# Battery_Charger.net
KiCad netlist of a schematic drawn in Altium Designer
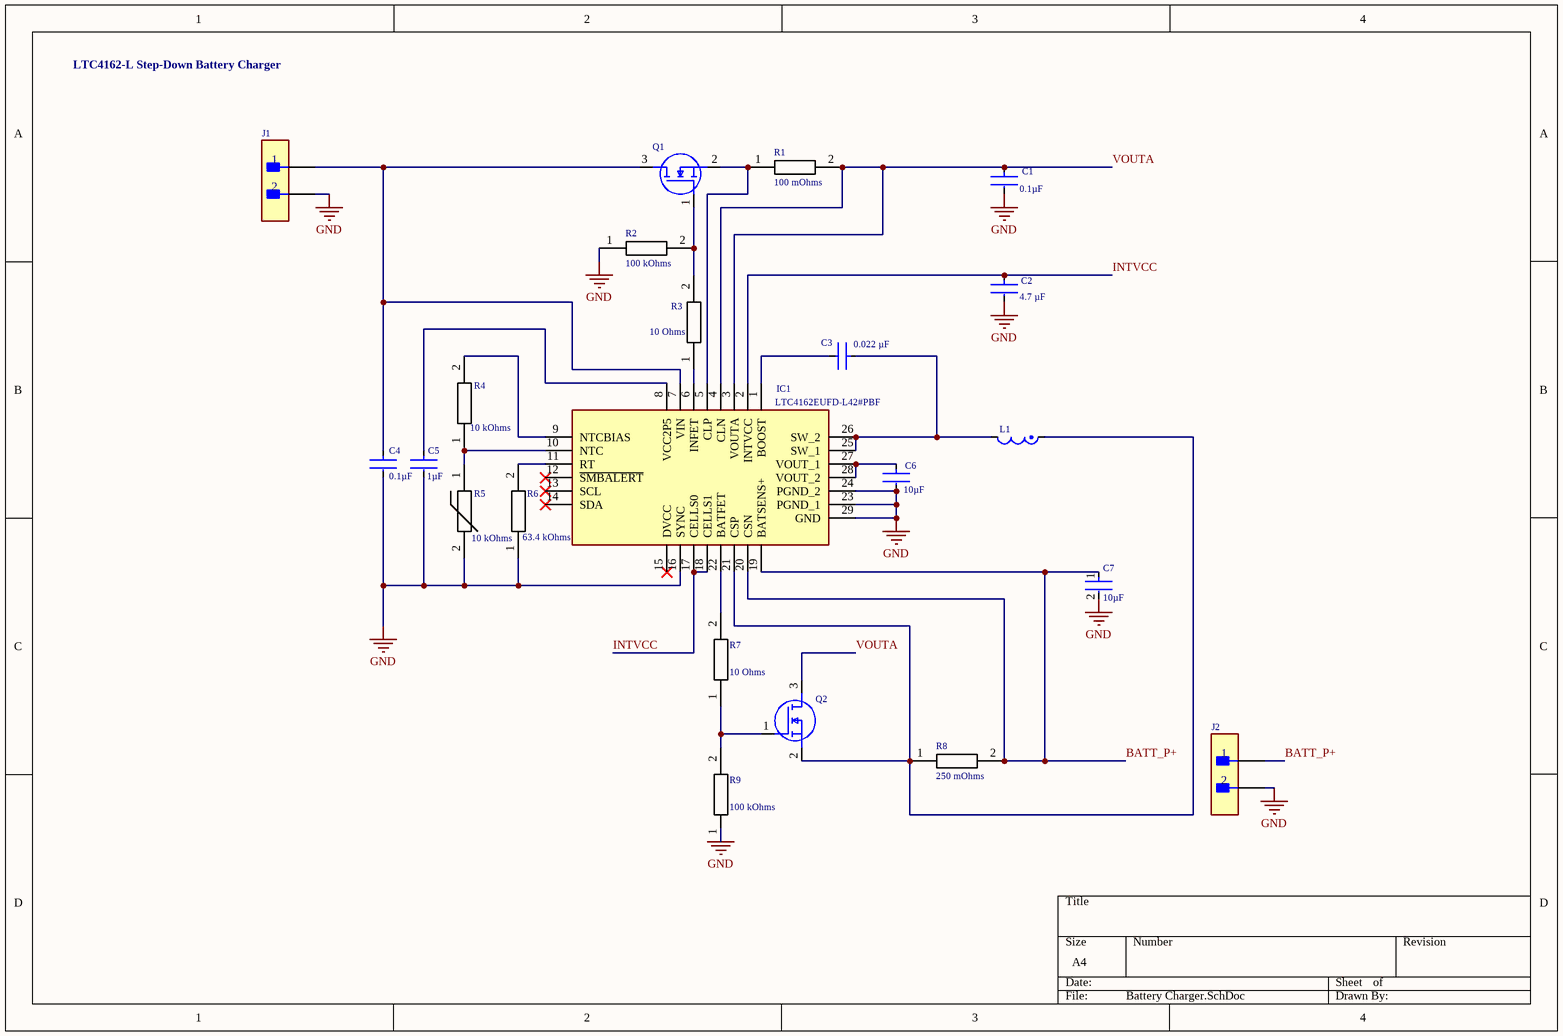
[diagram p0: Battery Charger.SchDoc]

(export (version "E")
  (design (tool "Eeschema 10.0.6"))
  (components
    (comp (ref "C1")
      (value "0.1µF")
      (footprint "FP-CC0603-DA-MFG")
      (description "CAP CER 0.1UF 16V X7R 0603 CC0603KRX7R7BB104")
      (fields
        (field (name "OCTOPART") "https://octopart.com/cc0603krx7r7bb104-yageo-192941")
        (field (name "TOLERANCE") "0.1")
      )
      (libsource (lib "Altium Content Vault") (part "11868f565c42a9108669ba33697ecf6"))
    )
    (comp (ref "C2")
      (value "4.7 µF")
      (footprint "FP-CC0603-DA-MFG")
      (description "CAP CER 4.7UF 10V X5R 0603 CC0603KRX5R6BB475")
      (fields (field (name "MANUFACTURER PART NUMBER") "CC0603KRX5R6BB475") (field (name "VOLTAGE") "10 V"))
      (libsource (lib "Altium Content Vault") (part "11868f565c42a9108669ba33697ecf6"))
    )
    (comp (ref "C3")
      (value "0.022 µF")
      (footprint "FP-C0603C-CF-MFG")
      (description "Ceramic Capacitor 0.022Uf 16V, X7R, 10%, 0603, Full Reel C0603C223K4RACTU")
      (fields
        (field (name "OCTOPART") "https://octopart.com/c0603c223k4ractu-kemet-123286")
        (field (name "MANUFACTURER PART NUMBER") "C0603C223K4RACTU")
      )
      (libsource (lib "Altium Content Vault") (part "b4654b650e69147ec39a6b967a45e02"))
    )
    (comp (ref "C4")
      (value "0.1µF")
      (footprint "FP-CC0603-DA-MFG")
      (description "CAP CER 0.1UF 16V X7R 0603 CC0603KRX7R7BB104")
      (fields
        (field (name "OCTOPART") "https://octopart.com/cc0603krx7r7bb104-yageo-192941")
        (field (name "TOLERANCE") "0.1")
      )
      (libsource (lib "Altium Content Vault") (part "11868f565c42a9108669ba33697ecf6"))
    )
    (comp (ref "C5")
      (value "1µF")
      (footprint "FP-CC0603-DA-MFG")
      (description "CAP CER 1UF 25V X5R 0603 CC0603KRX5R8BB105")
      (fields
        (field (name "OCTOPART") "https://octopart.com/cc0603krx5r8bb105-yageo-9292811")
        (field (name "MANUFACTURER") "YAGEO")
      )
      (libsource (lib "Altium Content Vault") (part "11868f565c42a9108669ba33697ecf6"))
    )
    (comp (ref "C6")
      (value "10µF")
      (footprint "FP-GRM21B-0_1-MFG")
      (fields (field (name "TOLERANCE") "10%") (field (name "VOLTAGE") "16V"))
      (libsource (lib "Altium Content Vault") (part "b4654b650e69147ec39a6b967a45e02"))
    )
    (comp (ref "C7")
      (value "10µF")
      (footprint "FP-GRM21B-0_1-MFG")
      (fields (field (name "TOLERANCE") "10%") (field (name "VOLTAGE") "16V"))
      (libsource (lib "") (part "b4654b650e69147ec39a6b967a45e02_1"))
    )
    (comp (ref "IC1")
      (value "LTC4162EUFD-L42#PBF")
      (footprint "SamacSys:QFN50P400X500X80-29N-D")
      (description "Integrated Circuit")
      (fields (field (name "MOUSER PART NUMBER") "584-4162EUFDL42PB"))
      (libsource (lib "SamacSys") (part "LTC4162EUFD-L42#PBF"))
    )
    (comp (ref "J1")
      (value "B2B-XH-A(LF)(SN)")
      (footprint "FP-B2B-XH-A_LF_SN-MFG")
      (description "CONN HEADER VERT 2POS 2.5MM")
      (libsource (lib "Altium Content Vault") (part "3bc925449376181038e59eaffc5286c"))
    )
    (comp (ref "J2")
      (value "B2B-XH-A(LF)(SN)")
      (footprint "FP-B2B-XH-A_LF_SN-MFG")
      (description "CONN HEADER VERT 2POS 2.5MM")
      (libsource (lib "Altium Content Vault") (part "3bc925449376181038e59eaffc5286c"))
    )
    (comp (ref "L1")
      (value "#B952AS-H-1R1N=P3")
      (footprint "FP-DS104C2-MFG")
      (description "Shielded Wirewound Inductor 1.1uH 30% 6000mA 0.011Ω SMD")
      (fields (field (name "TOLERANCE") "30%"))
      (libsource (lib "Altium Content Vault") (part "ae3b6ca10b736fc74204ce580bf9b8e"))
    )
    (comp (ref "Q1")
      (value "IRLML6344TRPBF")
      (footprint "SamacSys:SOT95P237X112-3N")
      (description "MOSFET (N-Channel)")
      (fields (field (name "MOUSER PART NUMBER") "942-IRLML6344TRPBF"))
      (libsource (lib "SamacSys") (part "IRLML6344TRPBF"))
    )
    (comp (ref "Q2")
      (value "IRLML6344TRPBF")
      (footprint "SamacSys:SOT95P237X112-3N")
      (description "MOSFET (N-Channel)")
      (fields (field (name "MOUSER PART NUMBER") "942-IRLML6344TRPBF"))
      (libsource (lib "SamacSys") (part "IRLML6344TRPBF"))
    )
    (comp (ref "R1")
      (value "100 mOhms")
      (footprint "PcbLib1:WSL2512R1000FEA Resistor")
      (libsource (lib "resistors") (part "WSL2512R1000FEA Resistor"))
    )
    (comp (ref "R2")
      (value "100 kOhms")
      (footprint "RC0603FR-07100KL Resistor")
      (description "100 kOhms ±1% 0.1W, 1/10W Chip Resistor 0603 (1608 Metric) Moisture Resistant Thick Film")
      (libsource (lib "resistors") (part "RC0603FR-07100KL Resistor"))
    )
    (comp (ref "R3")
      (value "10 Ohms")
      (footprint "RC0603FR-0710RL Resistor")
      (description "10 Ohms ±1% 0.1W, 1/10W Chip Resistor 0603 (1608 Metric) Moisture Resistant Thick Film")
      (libsource (lib "resistors") (part "RC0603FR-0710RL Resistor"))
    )
    (comp (ref "R4")
      (value "10 kOhms")
      (footprint "RC0603FR-0710KL")
      (description "10 kOhms ±1% 0.1W, 1/10W Chip Resistor 0603 (1608 Metric) Moisture Resistant Thick Film")
      (libsource (lib "resistors") (part "RC0603FR-0710KL Resistor"))
    )
    (comp (ref "R5")
      (value "10 kOhms")
      (footprint "NCP18XH103F03RB")
      (description "THERMISTOR NTC 10KOHM 3380K 0603")
      (libsource (lib "resistors") (part "NCP18XH103F03RB Resistor"))
    )
    (comp (ref "R6")
      (value "63.4 kOhms")
      (footprint "SamacSys:RESC1608X55N")
      (description "RC0603FR-0763K4L")
      (fields (field (name "MOUSER PART NUMBER") "603-RC0603FR-0763K4L"))
      (libsource (lib "*") (part "RC0603FR-0763K4L"))
    )
    (comp (ref "R7")
      (value "10 Ohms")
      (footprint "RC0603FR-0710RL Resistor")
      (description "10 Ohms ±1% 0.1W, 1/10W Chip Resistor 0603 (1608 Metric) Moisture Resistant Thick Film")
      (libsource (lib "resistors") (part "RC0603FR-0710RL Resistor"))
    )
    (comp (ref "R8")
      (value "250 mOhms")
      (footprint "SamacSys:RESC3216X89N")
      (description "WSL1206R2500FEA")
      (fields (field (name "MOUSER PART NUMBER") "71-WSL1206R2500FEA"))
      (libsource (lib "*") (part "WSL1206R2500FEA"))
    )
    (comp (ref "R9")
      (value "100 kOhms")
      (footprint "RC0603FR-07100KL Resistor")
      (description "100 kOhms ±1% 0.1W, 1/10W Chip Resistor 0603 (1608 Metric) Moisture Resistant Thick Film")
      (libsource (lib "resistors") (part "RC0603FR-07100KL Resistor"))
    )
  )
  (nets
    (net (code "1") (name "/BATT_P+") (class "Default")
      (node (ref "C7") (pin "1") (pinfunction "1_1") (pintype "passive"))
      (node (ref "IC1") (pin "19") (pinfunction "BATSENS+_19") (pintype "passive"))
      (node (ref "IC1") (pin "20") (pinfunction "CSN_20") (pintype "passive"))
      (node (ref "J2") (pin "1") (pinfunction "1_1") (pintype "passive"))
      (node (ref "R8") (pin "2") (pinfunction "2_2") (pintype "passive"))
    )
    (net (code "2") (name "/INTVCC") (class "Default")
      (node (ref "C2") (pin "1") (pinfunction "1_1") (pintype "passive"))
      (node (ref "IC1") (pin "17") (pinfunction "CELLS0_17") (pintype "passive"))
      (node (ref "IC1") (pin "18") (pinfunction "CELLS1_18") (pintype "passive"))
      (node (ref "IC1") (pin "2") (pinfunction "INTVCC_2") (pintype "passive"))
    )
    (net (code "3") (name "/VOUTA") (class "Default")
      (node (ref "C1") (pin "1") (pinfunction "1_1") (pintype "passive"))
      (node (ref "IC1") (pin "3") (pinfunction "VOUTA_3") (pintype "passive"))
      (node (ref "IC1") (pin "4") (pinfunction "CLN_4") (pintype "passive"))
      (node (ref "Q2") (pin "3") (pinfunction "D_3") (pintype "passive"))
      (node (ref "R1") (pin "2") (pinfunction "2_2") (pintype "passive"))
    )
    (net (code "4") (name "GND") (class "Default")
      (node (ref "C1") (pin "2") (pinfunction "2_2") (pintype "passive"))
      (node (ref "C2") (pin "2") (pinfunction "2_2") (pintype "passive"))
      (node (ref "C4") (pin "2") (pinfunction "2_2") (pintype "passive"))
      (node (ref "C5") (pin "2") (pinfunction "2_2") (pintype "passive"))
      (node (ref "C6") (pin "2") (pinfunction "2_2") (pintype "passive"))
      (node (ref "C7") (pin "2") (pinfunction "2_2") (pintype "passive"))
      (node (ref "IC1") (pin "16") (pinfunction "SYNC_16") (pintype "passive"))
      (node (ref "IC1") (pin "23") (pinfunction "PGND_1_23") (pintype "passive"))
      (node (ref "IC1") (pin "24") (pinfunction "PGND_2_24") (pintype "passive"))
      (node (ref "IC1") (pin "29") (pinfunction "GND_29") (pintype "passive"))
      (node (ref "J1") (pin "2") (pinfunction "2_2") (pintype "passive"))
      (node (ref "J2") (pin "2") (pinfunction "2_2") (pintype "passive"))
      (node (ref "R2") (pin "1") (pinfunction "1_1") (pintype "passive"))
      (node (ref "R5") (pin "2") (pinfunction "2_2") (pintype "passive"))
      (node (ref "R6") (pin "1") (pinfunction "1_1") (pintype "passive"))
      (node (ref "R9") (pin "1") (pinfunction "1_1") (pintype "passive"))
    )
    (net (code "5") (name "Net-(IC1-BATFET)") (class "Default")
      (node (ref "IC1") (pin "22") (pinfunction "BATFET_22") (pintype "passive"))
      (node (ref "R7") (pin "2") (pinfunction "2_2") (pintype "passive"))
    )
    (net (code "6") (name "Net-(IC1-BOOST)") (class "Default")
      (node (ref "C3") (pin "2") (pinfunction "2_2") (pintype "passive"))
      (node (ref "IC1") (pin "1") (pinfunction "BOOST_1") (pintype "passive"))
    )
    (net (code "7") (name "Net-(IC1-CLP)") (class "Default")
      (node (ref "IC1") (pin "5") (pinfunction "CLP_5") (pintype "passive"))
      (node (ref "Q1") (pin "2") (pinfunction "S_2") (pintype "passive"))
      (node (ref "R1") (pin "1") (pinfunction "1_1") (pintype "passive"))
    )
    (net (code "8") (name "Net-(IC1-CSP)") (class "Default")
      (node (ref "IC1") (pin "21") (pinfunction "CSP_21") (pintype "passive"))
      (node (ref "L1") (pin "1") (pinfunction "1_1") (pintype "passive"))
      (node (ref "Q2") (pin "2") (pinfunction "S_2") (pintype "passive"))
      (node (ref "R8") (pin "1") (pinfunction "1_1") (pintype "passive"))
    )
    (net (code "9") (name "Net-(IC1-INFET)") (class "Default")
      (node (ref "IC1") (pin "6") (pinfunction "INFET_6") (pintype "passive"))
      (node (ref "R3") (pin "1") (pinfunction "1_1") (pintype "passive"))
    )
    (net (code "10") (name "Net-(IC1-NTC)") (class "Default")
      (node (ref "IC1") (pin "10") (pinfunction "NTC_10") (pintype "passive"))
      (node (ref "R4") (pin "1") (pinfunction "1_1") (pintype "passive"))
      (node (ref "R5") (pin "1") (pinfunction "1_1") (pintype "passive"))
    )
    (net (code "11") (name "Net-(IC1-NTCBIAS)") (class "Default")
      (node (ref "IC1") (pin "9") (pinfunction "NTCBIAS_9") (pintype "passive"))
      (node (ref "R4") (pin "2") (pinfunction "2_2") (pintype "passive"))
    )
    (net (code "12") (name "Net-(IC1-RT)") (class "Default")
      (node (ref "IC1") (pin "11") (pinfunction "RT_11") (pintype "passive"))
      (node (ref "R6") (pin "2") (pinfunction "2_2") (pintype "passive"))
    )
    (net (code "13") (name "Net-(IC1-SW_1)") (class "Default")
      (node (ref "C3") (pin "1") (pinfunction "1_1") (pintype "passive"))
      (node (ref "IC1") (pin "25") (pinfunction "SW_1_25") (pintype "passive"))
      (node (ref "IC1") (pin "26") (pinfunction "SW_2_26") (pintype "passive"))
      (node (ref "L1") (pin "2") (pinfunction "2_2") (pintype "passive"))
    )
    (net (code "14") (name "Net-(IC1-VCC2P5)") (class "Default")
      (node (ref "C5") (pin "1") (pinfunction "1_1") (pintype "passive"))
      (node (ref "IC1") (pin "8") (pinfunction "VCC2P5_8") (pintype "passive"))
    )
    (net (code "15") (name "Net-(IC1-VIN)") (class "Default")
      (node (ref "C4") (pin "1") (pinfunction "1_1") (pintype "passive"))
      (node (ref "IC1") (pin "7") (pinfunction "VIN_7") (pintype "passive"))
      (node (ref "J1") (pin "1") (pinfunction "1_1") (pintype "passive"))
      (node (ref "Q1") (pin "3") (pinfunction "D_3") (pintype "passive"))
    )
    (net (code "16") (name "Net-(IC1-VOUT_1)") (class "Default")
      (node (ref "C6") (pin "1") (pinfunction "1_1") (pintype "passive"))
      (node (ref "IC1") (pin "27") (pinfunction "VOUT_1_27") (pintype "passive"))
      (node (ref "IC1") (pin "28") (pinfunction "VOUT_2_28") (pintype "passive"))
    )
    (net (code "17") (name "Net-(Q1-G)") (class "Default")
      (node (ref "Q1") (pin "1") (pinfunction "G_1") (pintype "passive"))
      (node (ref "R2") (pin "2") (pinfunction "2_2") (pintype "passive"))
      (node (ref "R3") (pin "2") (pinfunction "2_2") (pintype "passive"))
    )
    (net (code "18") (name "Net-(Q2-G)") (class "Default")
      (node (ref "Q2") (pin "1") (pinfunction "G_1") (pintype "passive"))
      (node (ref "R7") (pin "1") (pinfunction "1_1") (pintype "passive"))
      (node (ref "R9") (pin "2") (pinfunction "2_2") (pintype "passive"))
    )
    (net (code "19") (name "unconnected-(IC1-DVCC-Pad15)") (class "Default")
      (node (ref "IC1") (pin "15") (pinfunction "DVCC_15") (pintype "passive+no_connect"))
    )
    (net (code "20") (name "unconnected-(IC1-SCL-Pad13)") (class "Default")
      (node (ref "IC1") (pin "13") (pinfunction "SCL_13") (pintype "passive+no_connect"))
    )
    (net (code "21") (name "unconnected-(IC1-SDA-Pad14)") (class "Default")
      (node (ref "IC1") (pin "14") (pinfunction "SDA_14") (pintype "passive+no_connect"))
    )
    (net (code "22") (name "unconnected-(IC1-~{SMBALERT}-Pad12)") (class "Default")
      (node (ref "IC1") (pin "12") (pinfunction "~{SMBALERT}_12") (pintype "passive+no_connect"))
    )
  )
)
